# module.net
KiCad netlist of a schematic drawn in EAGLE
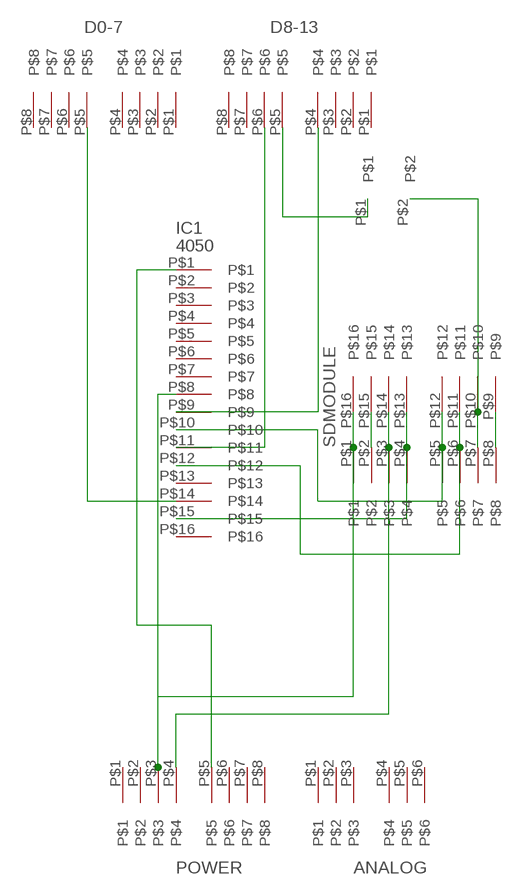
[diagram p0: schematic, sheet 1]

(export (version "E")
  (design (tool "Eeschema 10.0.6"))
  (components
    (comp (ref "ANALOG")
      (value "PINPLUG6PINPLUG6")
      (footprint "eagle-import:PINPLUG6")
      (libsource (lib "eagle-import") (part "PINPLUG6PINPLUG6"))
    )
    (comp (ref "D0-7")
      (value "PINPLUG8PINPLUG8")
      (footprint "eagle-import:PINPLUG8")
      (libsource (lib "eagle-import") (part "PINPLUG8PINPLUG8"))
    )
    (comp (ref "D8-13")
      (value "PINPLUG8PINPLUG8")
      (footprint "eagle-import:PINPLUG8")
      (libsource (lib "eagle-import") (part "PINPLUG8PINPLUG8"))
    )
    (comp (ref "IC1")
      (value "4050")
      (footprint "eagle-import:ICMOUNT16")
      (libsource (lib "eagle-import") (part "ICMOUNT16ICMOUNT16"))
    )
    (comp (ref "POWER")
      (value "PINPLUG8PINPLUG8")
      (footprint "eagle-import:PINPLUG8")
      (libsource (lib "eagle-import") (part "PINPLUG8PINPLUG8"))
    )
    (comp (ref "SDMODULE")
      (value "PINPLUG8X2PINPLUG8X2")
      (footprint "eagle-import:PINPLUG8X2")
      (libsource (lib "eagle-import") (part "PINPLUG8X2PINPLUG8X2"))
    )
    (comp (ref "U$1")
      (value "SHORTSHORT5")
      (footprint "eagle-import:SHORT5")
      (libsource (lib "eagle-import") (part "SHORTSHORT5"))
    )
  )
  (nets
    (net (code "1") (name "Net-(D0-7-PadP$5)") (class "Default")
      (node (ref "D0-7") (pin "P$5") (pinfunction "P$5_P$5") (pintype "bidirectional"))
      (node (ref "IC1") (pin "P$14") (pinfunction "P$14_P$14") (pintype "bidirectional"))
    )
    (net (code "2") (name "Net-(D8-13-PadP$4)") (class "Default")
      (node (ref "D8-13") (pin "P$4") (pinfunction "P$4_P$4") (pintype "bidirectional"))
      (node (ref "IC1") (pin "P$9") (pinfunction "P$9_P$9") (pintype "bidirectional"))
    )
    (net (code "3") (name "Net-(D8-13-PadP$5)") (class "Default")
      (node (ref "D8-13") (pin "P$5") (pinfunction "P$5_P$5") (pintype "bidirectional"))
      (node (ref "U$1") (pin "P$1") (pinfunction "P$1_P$1") (pintype "bidirectional"))
    )
    (net (code "4") (name "Net-(D8-13-PadP$6)") (class "Default")
      (node (ref "D8-13") (pin "P$6") (pinfunction "P$6_P$6") (pintype "bidirectional"))
      (node (ref "IC1") (pin "P$11") (pinfunction "P$11_P$11") (pintype "bidirectional"))
    )
    (net (code "5") (name "Net-(IC1-PadP$1)") (class "Default")
      (node (ref "IC1") (pin "P$1") (pinfunction "P$1_P$1") (pintype "bidirectional"))
      (node (ref "POWER") (pin "P$5") (pinfunction "P$5_P$5") (pintype "bidirectional"))
    )
    (net (code "6") (name "Net-(IC1-PadP$8)") (class "Default")
      (node (ref "IC1") (pin "P$8") (pinfunction "P$8_P$8") (pintype "bidirectional"))
      (node (ref "POWER") (pin "P$3") (pinfunction "P$3_P$3") (pintype "bidirectional"))
      (node (ref "SDMODULE") (pin "P$1") (pinfunction "P$1_P$1") (pintype "bidirectional"))
      (node (ref "SDMODULE") (pin "P$16") (pinfunction "P$16_P$16") (pintype "bidirectional"))
    )
    (net (code "7") (name "Net-(IC1-PadP$10)") (class "Default")
      (node (ref "IC1") (pin "P$10") (pinfunction "P$10_P$10") (pintype "bidirectional"))
      (node (ref "SDMODULE") (pin "P$12") (pinfunction "P$12_P$12") (pintype "bidirectional"))
      (node (ref "SDMODULE") (pin "P$5") (pinfunction "P$5_P$5") (pintype "bidirectional"))
    )
    (net (code "8") (name "Net-(IC1-PadP$12)") (class "Default")
      (node (ref "IC1") (pin "P$12") (pinfunction "P$12_P$12") (pintype "bidirectional"))
      (node (ref "SDMODULE") (pin "P$11") (pinfunction "P$11_P$11") (pintype "bidirectional"))
      (node (ref "SDMODULE") (pin "P$6") (pinfunction "P$6_P$6") (pintype "bidirectional"))
    )
    (net (code "9") (name "Net-(IC1-PadP$15)") (class "Default")
      (node (ref "IC1") (pin "P$15") (pinfunction "P$15_P$15") (pintype "bidirectional"))
      (node (ref "SDMODULE") (pin "P$13") (pinfunction "P$13_P$13") (pintype "bidirectional"))
      (node (ref "SDMODULE") (pin "P$4") (pinfunction "P$4_P$4") (pintype "bidirectional"))
    )
    (net (code "10") (name "Net-(POWER-PadP$4)") (class "Default")
      (node (ref "POWER") (pin "P$4") (pinfunction "P$4_P$4") (pintype "bidirectional"))
      (node (ref "SDMODULE") (pin "P$14") (pinfunction "P$14_P$14") (pintype "bidirectional"))
      (node (ref "SDMODULE") (pin "P$3") (pinfunction "P$3_P$3") (pintype "bidirectional"))
    )
    (net (code "11") (name "Net-(SDMODULE-PadP$8)") (class "Default")
      (node (ref "SDMODULE") (pin "P$8") (pinfunction "P$8_P$8") (pintype "bidirectional"))
      (node (ref "SDMODULE") (pin "P$9") (pinfunction "P$9_P$9") (pintype "bidirectional"))
    )
    (net (code "12") (name "Net-(SDMODULE-PadP$10)") (class "Default")
      (node (ref "SDMODULE") (pin "P$10") (pinfunction "P$10_P$10") (pintype "bidirectional"))
      (node (ref "SDMODULE") (pin "P$7") (pinfunction "P$7_P$7") (pintype "bidirectional"))
      (node (ref "U$1") (pin "P$2") (pinfunction "P$2_P$2") (pintype "bidirectional"))
    )
    (net (code "13") (name "Net-(SDMODULE-PadP$15)") (class "Default")
      (node (ref "SDMODULE") (pin "P$15") (pinfunction "P$15_P$15") (pintype "bidirectional"))
      (node (ref "SDMODULE") (pin "P$2") (pinfunction "P$2_P$2") (pintype "bidirectional"))
    )
    (net (code "14") (name "unconnected-(ANALOG-PadP$1)") (class "Default")
      (node (ref "ANALOG") (pin "P$1") (pinfunction "P$1_P$1") (pintype "bidirectional"))
    )
    (net (code "15") (name "unconnected-(ANALOG-PadP$2)") (class "Default")
      (node (ref "ANALOG") (pin "P$2") (pinfunction "P$2_P$2") (pintype "bidirectional"))
    )
    (net (code "16") (name "unconnected-(ANALOG-PadP$3)") (class "Default")
      (node (ref "ANALOG") (pin "P$3") (pinfunction "P$3_P$3") (pintype "bidirectional"))
    )
    (net (code "17") (name "unconnected-(ANALOG-PadP$4)") (class "Default")
      (node (ref "ANALOG") (pin "P$4") (pinfunction "P$4_P$4") (pintype "bidirectional"))
    )
    (net (code "18") (name "unconnected-(ANALOG-PadP$5)") (class "Default")
      (node (ref "ANALOG") (pin "P$5") (pinfunction "P$5_P$5") (pintype "bidirectional"))
    )
    (net (code "19") (name "unconnected-(ANALOG-PadP$6)") (class "Default")
      (node (ref "ANALOG") (pin "P$6") (pinfunction "P$6_P$6") (pintype "bidirectional"))
    )
    (net (code "20") (name "unconnected-(D0-7-PadP$1)") (class "Default")
      (node (ref "D0-7") (pin "P$1") (pinfunction "P$1_P$1") (pintype "bidirectional"))
    )
    (net (code "21") (name "unconnected-(D0-7-PadP$2)") (class "Default")
      (node (ref "D0-7") (pin "P$2") (pinfunction "P$2_P$2") (pintype "bidirectional"))
    )
    (net (code "22") (name "unconnected-(D0-7-PadP$3)") (class "Default")
      (node (ref "D0-7") (pin "P$3") (pinfunction "P$3_P$3") (pintype "bidirectional"))
    )
    (net (code "23") (name "unconnected-(D0-7-PadP$4)") (class "Default")
      (node (ref "D0-7") (pin "P$4") (pinfunction "P$4_P$4") (pintype "bidirectional"))
    )
    (net (code "24") (name "unconnected-(D0-7-PadP$6)") (class "Default")
      (node (ref "D0-7") (pin "P$6") (pinfunction "P$6_P$6") (pintype "bidirectional"))
    )
    (net (code "25") (name "unconnected-(D0-7-PadP$7)") (class "Default")
      (node (ref "D0-7") (pin "P$7") (pinfunction "P$7_P$7") (pintype "bidirectional"))
    )
    (net (code "26") (name "unconnected-(D0-7-PadP$8)") (class "Default")
      (node (ref "D0-7") (pin "P$8") (pinfunction "P$8_P$8") (pintype "bidirectional"))
    )
    (net (code "27") (name "unconnected-(D8-13-PadP$1)") (class "Default")
      (node (ref "D8-13") (pin "P$1") (pinfunction "P$1_P$1") (pintype "bidirectional"))
    )
    (net (code "28") (name "unconnected-(D8-13-PadP$2)") (class "Default")
      (node (ref "D8-13") (pin "P$2") (pinfunction "P$2_P$2") (pintype "bidirectional"))
    )
    (net (code "29") (name "unconnected-(D8-13-PadP$3)") (class "Default")
      (node (ref "D8-13") (pin "P$3") (pinfunction "P$3_P$3") (pintype "bidirectional"))
    )
    (net (code "30") (name "unconnected-(D8-13-PadP$7)") (class "Default")
      (node (ref "D8-13") (pin "P$7") (pinfunction "P$7_P$7") (pintype "bidirectional"))
    )
    (net (code "31") (name "unconnected-(D8-13-PadP$8)") (class "Default")
      (node (ref "D8-13") (pin "P$8") (pinfunction "P$8_P$8") (pintype "bidirectional"))
    )
    (net (code "32") (name "unconnected-(IC1-PadP$2)") (class "Default")
      (node (ref "IC1") (pin "P$2") (pinfunction "P$2_P$2") (pintype "bidirectional"))
    )
    (net (code "33") (name "unconnected-(IC1-PadP$3)") (class "Default")
      (node (ref "IC1") (pin "P$3") (pinfunction "P$3_P$3") (pintype "bidirectional"))
    )
    (net (code "34") (name "unconnected-(IC1-PadP$4)") (class "Default")
      (node (ref "IC1") (pin "P$4") (pinfunction "P$4_P$4") (pintype "bidirectional"))
    )
    (net (code "35") (name "unconnected-(IC1-PadP$5)") (class "Default")
      (node (ref "IC1") (pin "P$5") (pinfunction "P$5_P$5") (pintype "bidirectional"))
    )
    (net (code "36") (name "unconnected-(IC1-PadP$6)") (class "Default")
      (node (ref "IC1") (pin "P$6") (pinfunction "P$6_P$6") (pintype "bidirectional"))
    )
    (net (code "37") (name "unconnected-(IC1-PadP$7)") (class "Default")
      (node (ref "IC1") (pin "P$7") (pinfunction "P$7_P$7") (pintype "bidirectional"))
    )
    (net (code "38") (name "unconnected-(IC1-PadP$13)") (class "Default")
      (node (ref "IC1") (pin "P$13") (pinfunction "P$13_P$13") (pintype "bidirectional"))
    )
    (net (code "39") (name "unconnected-(IC1-PadP$16)") (class "Default")
      (node (ref "IC1") (pin "P$16") (pinfunction "P$16_P$16") (pintype "bidirectional"))
    )
    (net (code "40") (name "unconnected-(POWER-PadP$1)") (class "Default")
      (node (ref "POWER") (pin "P$1") (pinfunction "P$1_P$1") (pintype "bidirectional"))
    )
    (net (code "41") (name "unconnected-(POWER-PadP$2)") (class "Default")
      (node (ref "POWER") (pin "P$2") (pinfunction "P$2_P$2") (pintype "bidirectional"))
    )
    (net (code "42") (name "unconnected-(POWER-PadP$6)") (class "Default")
      (node (ref "POWER") (pin "P$6") (pinfunction "P$6_P$6") (pintype "bidirectional"))
    )
    (net (code "43") (name "unconnected-(POWER-PadP$7)") (class "Default")
      (node (ref "POWER") (pin "P$7") (pinfunction "P$7_P$7") (pintype "bidirectional"))
    )
    (net (code "44") (name "unconnected-(POWER-PadP$8)") (class "Default")
      (node (ref "POWER") (pin "P$8") (pinfunction "P$8_P$8") (pintype "bidirectional"))
    )
  )
)
